# RELAY1.net
KiCad netlist of a schematic drawn in Altium Designer
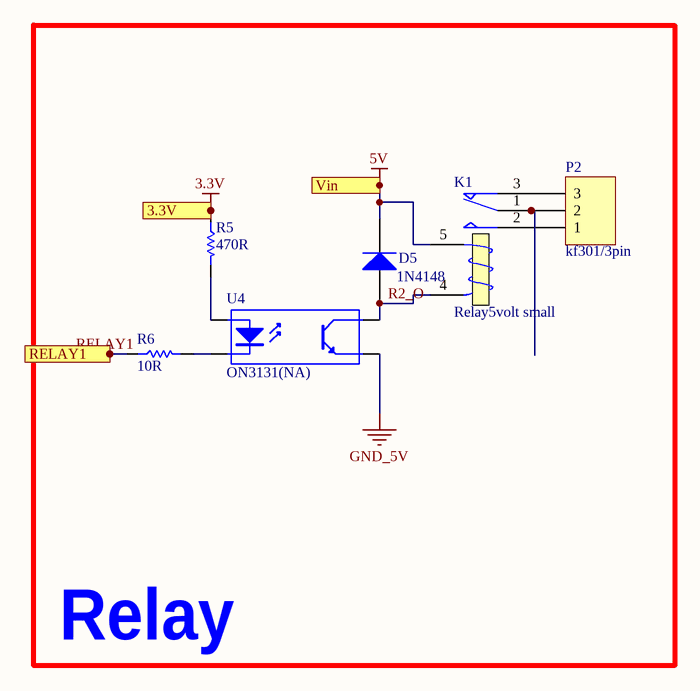
[diagram p0: RELAY1.SchDoc]

(export (version "E")
  (design (tool "Eeschema 10.0.6"))
  (components
    (comp (ref "D5")
      (value "1N4148")
      (footprint "sod123")
      (description "1 Amp General Purpose Rectifier")
      (fields (field (name "PUBLISHER") "Altium Limited"))
      (libsource (lib "Miscellaneous Devices") (part "Diode 1N4007"))
    )
    (comp (ref "K1")
      (value "Relay5volt small")
      (footprint "relay5_childern")
      (description "SPDT Relay")
      (fields (field (name "PUBLISHER") "Altium Limited"))
      (libsource (lib "FLIB") (part "Relay"))
    )
    (comp (ref "P2")
      (value "kf301/3pin")
      (footprint "Blue Connector 1*3 -kf301")
      (fields (field (name "PUBLISHER") "Altium Limited"))
      (libsource (lib "Miscellaneous Connectors") (part "Header 3"))
    )
    (comp (ref "R5")
      (value "470R")
      (footprint "0805/resistor")
      (description "Resistor")
      (fields (field (name "TOLERANCE") "5%") (field (name "POWER") "1/8 W"))
      (libsource (lib "skille") (part "Resistor"))
    )
    (comp (ref "R6")
      (value "10R")
      (footprint "0805/resistor")
      (description "Resistor")
      (fields (field (name "TOLERANCE") "5%") (field (name "POWER") "1/8 W"))
      (libsource (lib "skille") (part "Resistor"))
    )
    (comp (ref "U4")
      (value "ON3131(NA)")
      (footprint "OPTO_COUPLER")
      (description "4-Pin Phototransistor Optocoupler")
      (fields (field (name "PUBLISHER") "Altium Limited"))
      (libsource (lib "skille") (part "Optoisolator1"))
    )
  )
  (nets
    (net (code "1") (name "/R2_O") (class "Default")
      (node (ref "D5") (pin "A") (pinfunction "A_A") (pintype "passive"))
      (node (ref "K1") (pin "4") (pinfunction "T2_4") (pintype "passive"))
      (node (ref "U4") (pin "4") (pinfunction "C_4") (pintype "passive"))
    )
    (net (code "2") (name "/RELAY1") (class "Default")
      (node (ref "R6") (pin "1") (pinfunction "1_1") (pintype "passive"))
    )
    (net (code "3") (name "3.3V") (class "Default")
      (node (ref "R5") (pin "1") (pinfunction "1_1") (pintype "passive"))
    )
    (net (code "4") (name "5V") (class "Default")
      (node (ref "D5") (pin "K") (pinfunction "K_K") (pintype "passive"))
      (node (ref "K1") (pin "5") (pinfunction "5_5") (pintype "passive"))
    )
    (net (code "5") (name "GND_5V") (class "Default")
      (node (ref "U4") (pin "3") (pinfunction "E_3") (pintype "passive"))
    )
    (net (code "6") (name "Net-(K1-COM)") (class "Default")
      (node (ref "K1") (pin "1") (pinfunction "COM_1") (pintype "passive"))
      (node (ref "P2") (pin "2") (pinfunction "2_2") (pintype "passive"))
    )
    (net (code "7") (name "Net-(K1-NO)") (class "Default")
      (node (ref "K1") (pin "2") (pinfunction "NO_2") (pintype "passive"))
      (node (ref "P2") (pin "1") (pinfunction "1_1") (pintype "passive"))
    )
    (net (code "8") (name "Net-(K1-T1)") (class "Default")
      (node (ref "K1") (pin "3") (pinfunction "T1_3") (pintype "passive"))
      (node (ref "P2") (pin "3") (pinfunction "3_3") (pintype "passive"))
    )
    (net (code "9") (name "Net-(U4-A)") (class "Default")
      (node (ref "R5") (pin "2") (pinfunction "2_2") (pintype "passive"))
      (node (ref "U4") (pin "1") (pinfunction "A_1") (pintype "passive"))
    )
    (net (code "10") (name "Net-(U4-K)") (class "Default")
      (node (ref "R6") (pin "2") (pinfunction "2_2") (pintype "passive"))
      (node (ref "U4") (pin "2") (pinfunction "K_2") (pintype "passive"))
    )
  )
)
